# SCH_Schematic-PCB-Design-FC-TD2_2026-04-.net
KiCad netlist of a schematic drawn in EasyEDA
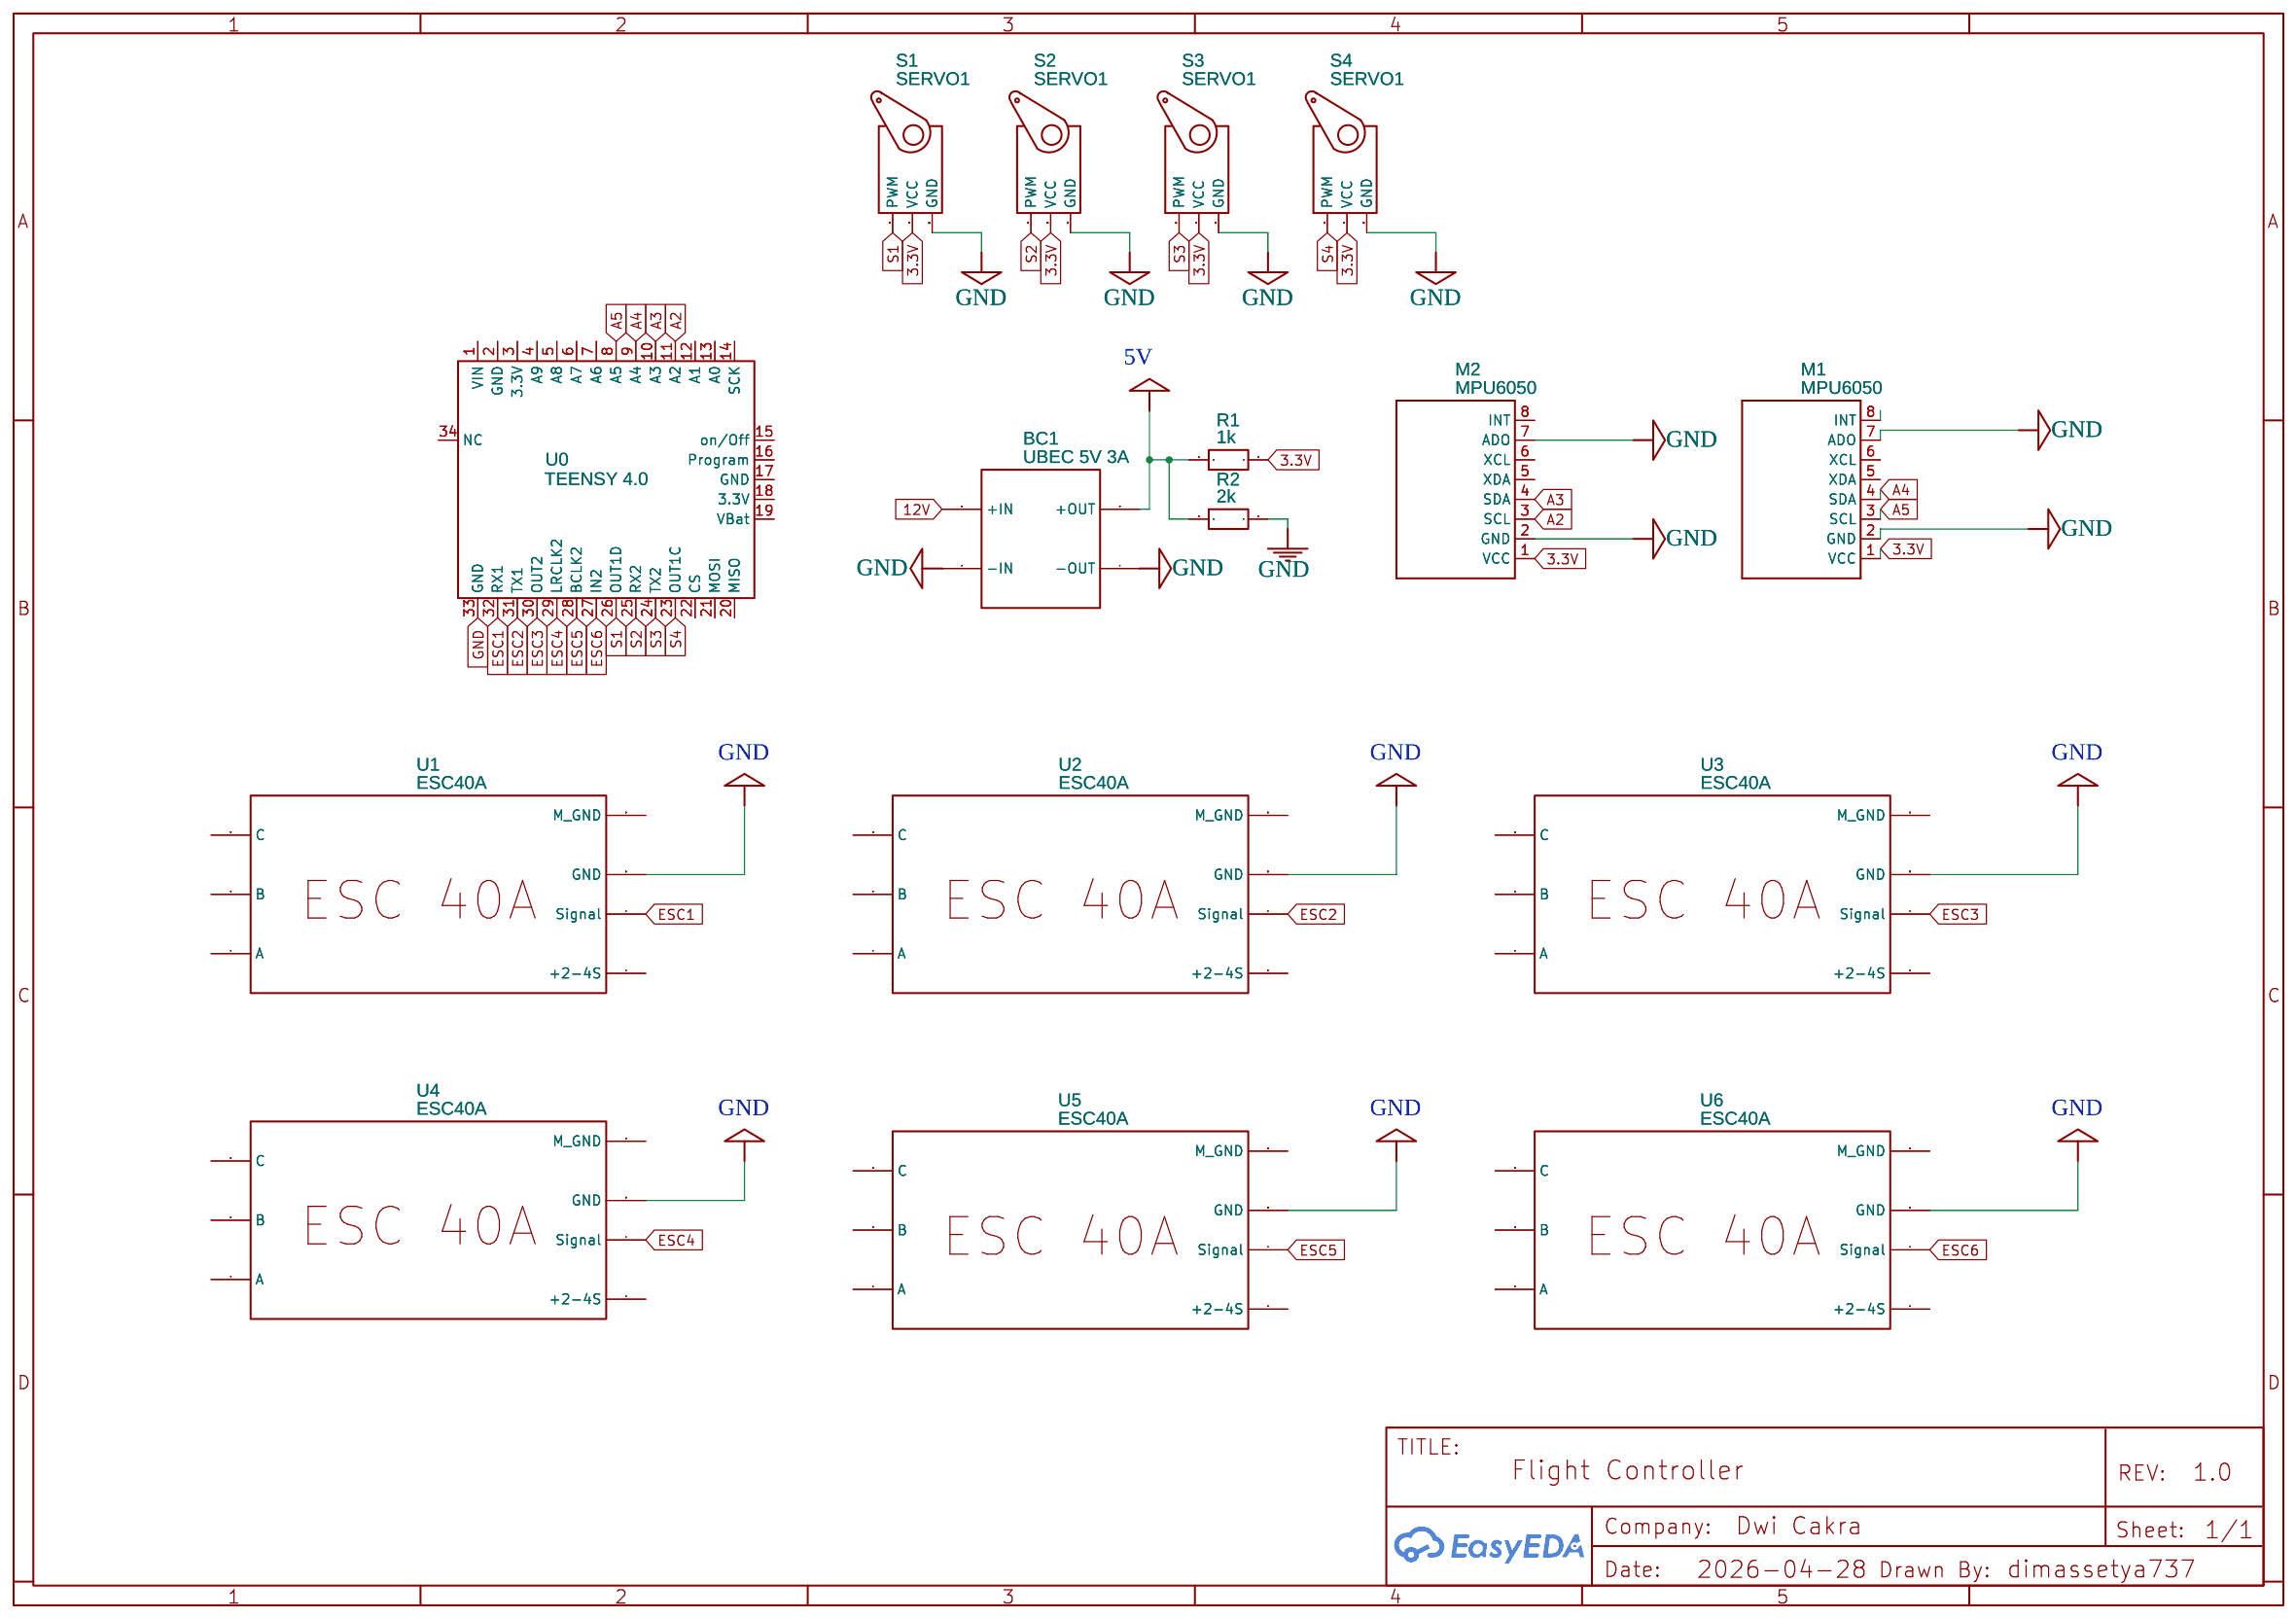
[diagram p0: schematic sheet]

(export (version "E")
  (design (tool "Eeschema 10.0.6"))
  (components
    (comp (ref "BC1") (value "UBEC 5V 3A") (libsource (lib "") (part "UBEC 5V 3A")))
    (comp (ref "M1") (value "MPU6050") (libsource (lib "") (part "MPU6050")))
    (comp (ref "M2") (value "MPU6050") (libsource (lib "") (part "MPU6050")))
    (comp (ref "R1")
      (value "1k")
      (fields (field (name "Manufacturer Part") "贴片电阻ChipResistors"))
      (libsource (lib "") (part "贴片电阻CHIPRESISTORS"))
    )
    (comp (ref "R2")
      (value "2k")
      (fields (field (name "Manufacturer Part") "贴片电阻ChipResistors"))
      (libsource (lib "") (part "贴片电阻CHIPRESISTORS"))
    )
    (comp (ref "S1") (value "SERVO1") (libsource (lib "") (part "SERVO MG90S")))
    (comp (ref "S2") (value "SERVO1") (libsource (lib "") (part "SERVO MG90S")))
    (comp (ref "S3") (value "SERVO1") (libsource (lib "") (part "SERVO MG90S")))
    (comp (ref "S4") (value "SERVO1") (libsource (lib "") (part "SERVO MG90S")))
    (comp (ref "U0")
      (value "TEENSY 4.0")
      (fields (field (name "Manufacturer Part") "Teensy 4.0"))
      (libsource (lib "") (part "TEENSY 4.0"))
    )
    (comp (ref "U1") (value "ESC40A") (libsource (lib "") (part "ESC40A_1")))
    (comp (ref "U2") (value "ESC40A") (libsource (lib "") (part "ESC40A_1")))
    (comp (ref "U3") (value "ESC40A") (libsource (lib "") (part "ESC40A_1")))
    (comp (ref "U4") (value "ESC40A") (libsource (lib "") (part "ESC40A_1")))
    (comp (ref "U5") (value "ESC40A") (libsource (lib "") (part "ESC40A")))
    (comp (ref "U6") (value "ESC40A") (libsource (lib "") (part "ESC40A")))
  )
  (nets
    (net (code "1") (name "3.3V") (class "Default")
      (node (ref "M1") (pin "1") (pinfunction "VCC_1") (pintype "bidirectional"))
      (node (ref "M2") (pin "1") (pinfunction "VCC_1") (pintype "bidirectional"))
      (node (ref "R1") (pin "2") (pinfunction "2_2") (pintype "unspecified"))
      (node (ref "S1") (pin "VCC") (pinfunction "VCC_VCC") (pintype "unspecified"))
      (node (ref "S2") (pin "VCC") (pinfunction "VCC_VCC") (pintype "unspecified"))
      (node (ref "S3") (pin "VCC") (pinfunction "VCC_VCC") (pintype "unspecified"))
      (node (ref "S4") (pin "VCC") (pinfunction "VCC_VCC") (pintype "unspecified"))
    )
    (net (code "2") (name "5V") (class "Default")
      (node (ref "BC1") (pin "3") (pinfunction "+OUT_3") (pintype "unspecified"))
      (node (ref "R1") (pin "1") (pinfunction "1_1") (pintype "unspecified"))
      (node (ref "R2") (pin "1") (pinfunction "1_1") (pintype "unspecified"))
    )
    (net (code "3") (name "12V") (class "Default")
      (node (ref "BC1") (pin "2") (pinfunction "+IN_2") (pintype "unspecified"))
    )
    (net (code "4") (name "A2") (class "Default")
      (node (ref "M2") (pin "3") (pinfunction "SCL_3") (pintype "bidirectional"))
      (node (ref "U0") (pin "11") (pinfunction "A2_11") (pintype "unspecified"))
    )
    (net (code "5") (name "A3") (class "Default")
      (node (ref "M2") (pin "4") (pinfunction "SDA_4") (pintype "bidirectional"))
      (node (ref "U0") (pin "10") (pinfunction "A3_10") (pintype "unspecified"))
    )
    (net (code "6") (name "A4") (class "Default")
      (node (ref "M1") (pin "4") (pinfunction "SDA_4") (pintype "bidirectional"))
      (node (ref "U0") (pin "9") (pinfunction "A4_9") (pintype "unspecified"))
    )
    (net (code "7") (name "A5") (class "Default")
      (node (ref "M1") (pin "3") (pinfunction "SCL_3") (pintype "bidirectional"))
      (node (ref "U0") (pin "8") (pinfunction "A5_8") (pintype "unspecified"))
    )
    (net (code "8") (name "ESC1") (class "Default")
      (node (ref "U0") (pin "32") (pinfunction "RX1_32") (pintype "unspecified"))
      (node (ref "U1") (pin "7") (pinfunction "Signal_7") (pintype "unspecified"))
    )
    (net (code "9") (name "ESC2") (class "Default")
      (node (ref "U0") (pin "31") (pinfunction "TX1_31") (pintype "unspecified"))
      (node (ref "U2") (pin "7") (pinfunction "Signal_7") (pintype "unspecified"))
    )
    (net (code "10") (name "ESC3") (class "Default")
      (node (ref "U0") (pin "30") (pinfunction "OUT2_30") (pintype "unspecified"))
      (node (ref "U3") (pin "7") (pinfunction "Signal_7") (pintype "unspecified"))
    )
    (net (code "11") (name "ESC4") (class "Default")
      (node (ref "U0") (pin "29") (pinfunction "LRCLK2_29") (pintype "unspecified"))
      (node (ref "U4") (pin "7") (pinfunction "Signal_7") (pintype "unspecified"))
    )
    (net (code "12") (name "ESC5") (class "Default")
      (node (ref "U0") (pin "28") (pinfunction "BCLK2_28") (pintype "unspecified"))
      (node (ref "U5") (pin "7") (pinfunction "Signal_7") (pintype "unspecified"))
    )
    (net (code "13") (name "ESC6") (class "Default")
      (node (ref "U0") (pin "27") (pinfunction "IN2_27") (pintype "unspecified"))
      (node (ref "U6") (pin "7") (pinfunction "Signal_7") (pintype "unspecified"))
    )
    (net (code "14") (name "GND") (class "Default")
      (node (ref "BC1") (pin "1") (pinfunction "-IN_1") (pintype "unspecified"))
      (node (ref "BC1") (pin "4") (pinfunction "-OUT_4") (pintype "unspecified"))
      (node (ref "M1") (pin "2") (pinfunction "GND_2") (pintype "bidirectional"))
      (node (ref "M1") (pin "7") (pinfunction "ADO_7") (pintype "bidirectional"))
      (node (ref "M2") (pin "2") (pinfunction "GND_2") (pintype "bidirectional"))
      (node (ref "M2") (pin "7") (pinfunction "ADO_7") (pintype "bidirectional"))
      (node (ref "R2") (pin "2") (pinfunction "2_2") (pintype "unspecified"))
      (node (ref "S1") (pin "GND") (pinfunction "GND_GND") (pintype "unspecified"))
      (node (ref "S2") (pin "GND") (pinfunction "GND_GND") (pintype "unspecified"))
      (node (ref "S3") (pin "GND") (pinfunction "GND_GND") (pintype "unspecified"))
      (node (ref "S4") (pin "GND") (pinfunction "GND_GND") (pintype "unspecified"))
      (node (ref "U0") (pin "33") (pinfunction "GND_33") (pintype "unspecified"))
      (node (ref "U1") (pin "6") (pinfunction "GND_6") (pintype "unspecified"))
      (node (ref "U2") (pin "6") (pinfunction "GND_6") (pintype "unspecified"))
      (node (ref "U3") (pin "6") (pinfunction "GND_6") (pintype "unspecified"))
      (node (ref "U4") (pin "6") (pinfunction "GND_6") (pintype "unspecified"))
      (node (ref "U5") (pin "6") (pinfunction "GND_6") (pintype "unspecified"))
      (node (ref "U6") (pin "6") (pinfunction "GND_6") (pintype "unspecified"))
    )
    (net (code "15") (name "S1") (class "Default")
      (node (ref "S1") (pin "PWM") (pinfunction "PWM_PWM") (pintype "unspecified"))
      (node (ref "U0") (pin "26") (pinfunction "OUT1D_26") (pintype "unspecified"))
    )
    (net (code "16") (name "S2") (class "Default")
      (node (ref "S2") (pin "PWM") (pinfunction "PWM_PWM") (pintype "unspecified"))
      (node (ref "U0") (pin "25") (pinfunction "RX2_25") (pintype "unspecified"))
    )
    (net (code "17") (name "S3") (class "Default")
      (node (ref "S3") (pin "PWM") (pinfunction "PWM_PWM") (pintype "unspecified"))
      (node (ref "U0") (pin "24") (pinfunction "TX2_24") (pintype "unspecified"))
    )
    (net (code "18") (name "S4") (class "Default")
      (node (ref "S4") (pin "PWM") (pinfunction "PWM_PWM") (pintype "unspecified"))
      (node (ref "U0") (pin "23") (pinfunction "OUT1C_23") (pintype "unspecified"))
    )
    (net (code "19") (name "unconnected-(M1-INT-Pad8)") (class "Default")
      (node (ref "M1") (pin "8") (pinfunction "INT_8") (pintype "bidirectional"))
    )
    (net (code "20") (name "unconnected-(M1-XCL-Pad6)") (class "Default")
      (node (ref "M1") (pin "6") (pinfunction "XCL_6") (pintype "bidirectional"))
    )
    (net (code "21") (name "unconnected-(M1-XDA-Pad5)") (class "Default")
      (node (ref "M1") (pin "5") (pinfunction "XDA_5") (pintype "bidirectional"))
    )
    (net (code "22") (name "unconnected-(M2-INT-Pad8)") (class "Default")
      (node (ref "M2") (pin "8") (pinfunction "INT_8") (pintype "bidirectional"))
    )
    (net (code "23") (name "unconnected-(M2-XCL-Pad6)") (class "Default")
      (node (ref "M2") (pin "6") (pinfunction "XCL_6") (pintype "bidirectional"))
    )
    (net (code "24") (name "unconnected-(M2-XDA-Pad5)") (class "Default")
      (node (ref "M2") (pin "5") (pinfunction "XDA_5") (pintype "bidirectional"))
    )
    (net (code "25") (name "unconnected-(U0-3.3V-Pad3)") (class "Default")
      (node (ref "U0") (pin "3") (pinfunction "3.3V_3") (pintype "unspecified"))
    )
    (net (code "26") (name "unconnected-(U0-3.3V-Pad18)") (class "Default")
      (node (ref "U0") (pin "18") (pinfunction "3.3V_18") (pintype "unspecified"))
    )
    (net (code "27") (name "unconnected-(U0-A0-Pad13)") (class "Default")
      (node (ref "U0") (pin "13") (pinfunction "A0_13") (pintype "unspecified"))
    )
    (net (code "28") (name "unconnected-(U0-A1-Pad12)") (class "Default")
      (node (ref "U0") (pin "12") (pinfunction "A1_12") (pintype "unspecified"))
    )
    (net (code "29") (name "unconnected-(U0-A6-Pad7)") (class "Default")
      (node (ref "U0") (pin "7") (pinfunction "A6_7") (pintype "unspecified"))
    )
    (net (code "30") (name "unconnected-(U0-A7-Pad6)") (class "Default")
      (node (ref "U0") (pin "6") (pinfunction "A7_6") (pintype "unspecified"))
    )
    (net (code "31") (name "unconnected-(U0-A8-Pad5)") (class "Default")
      (node (ref "U0") (pin "5") (pinfunction "A8_5") (pintype "unspecified"))
    )
    (net (code "32") (name "unconnected-(U0-A9-Pad4)") (class "Default")
      (node (ref "U0") (pin "4") (pinfunction "A9_4") (pintype "unspecified"))
    )
    (net (code "33") (name "unconnected-(U0-CS-Pad22)") (class "Default")
      (node (ref "U0") (pin "22") (pinfunction "CS_22") (pintype "unspecified"))
    )
    (net (code "34") (name "unconnected-(U0-GND-Pad2)") (class "Default")
      (node (ref "U0") (pin "2") (pinfunction "GND_2") (pintype "unspecified"))
    )
    (net (code "35") (name "unconnected-(U0-GND-Pad17)") (class "Default")
      (node (ref "U0") (pin "17") (pinfunction "GND_17") (pintype "unspecified"))
    )
    (net (code "36") (name "unconnected-(U0-MISO-Pad20)") (class "Default")
      (node (ref "U0") (pin "20") (pinfunction "MISO_20") (pintype "unspecified"))
    )
    (net (code "37") (name "unconnected-(U0-MOSI-Pad21)") (class "Default")
      (node (ref "U0") (pin "21") (pinfunction "MOSI_21") (pintype "unspecified"))
    )
    (net (code "38") (name "unconnected-(U0-NC-Pad34)") (class "Default")
      (node (ref "U0") (pin "34") (pinfunction "NC_34") (pintype "unspecified"))
    )
    (net (code "39") (name "unconnected-(U0-Program-Pad16)") (class "Default")
      (node (ref "U0") (pin "16") (pinfunction "Program_16") (pintype "unspecified"))
    )
    (net (code "40") (name "unconnected-(U0-SCK-Pad14)") (class "Default")
      (node (ref "U0") (pin "14") (pinfunction "SCK_14") (pintype "unspecified"))
    )
    (net (code "41") (name "unconnected-(U0-VBat-Pad19)") (class "Default")
      (node (ref "U0") (pin "19") (pinfunction "VBat_19") (pintype "unspecified"))
    )
    (net (code "42") (name "unconnected-(U0-VIN-Pad1)") (class "Default")
      (node (ref "U0") (pin "1") (pinfunction "VIN_1") (pintype "unspecified"))
    )
    (net (code "43") (name "unconnected-(U0-on{slash}Off-Pad15)") (class "Default")
      (node (ref "U0") (pin "15") (pinfunction "on/Off_15") (pintype "unspecified"))
    )
    (net (code "44") (name "unconnected-(U1-+2-4S-Pad4)") (class "Default")
      (node (ref "U1") (pin "4") (pinfunction "+2-4S_4") (pintype "unspecified"))
    )
    (net (code "45") (name "unconnected-(U1-A-Pad1)") (class "Default")
      (node (ref "U1") (pin "1") (pinfunction "A_1") (pintype "unspecified"))
    )
    (net (code "46") (name "unconnected-(U1-B-Pad2)") (class "Default")
      (node (ref "U1") (pin "2") (pinfunction "B_2") (pintype "unspecified"))
    )
    (net (code "47") (name "unconnected-(U1-C-Pad3)") (class "Default")
      (node (ref "U1") (pin "3") (pinfunction "C_3") (pintype "unspecified"))
    )
    (net (code "48") (name "unconnected-(U1-M_GND-Pad5)") (class "Default")
      (node (ref "U1") (pin "5") (pinfunction "M_GND_5") (pintype "unspecified"))
    )
    (net (code "49") (name "unconnected-(U2-+2-4S-Pad4)") (class "Default")
      (node (ref "U2") (pin "4") (pinfunction "+2-4S_4") (pintype "unspecified"))
    )
    (net (code "50") (name "unconnected-(U2-A-Pad1)") (class "Default")
      (node (ref "U2") (pin "1") (pinfunction "A_1") (pintype "unspecified"))
    )
    (net (code "51") (name "unconnected-(U2-B-Pad2)") (class "Default")
      (node (ref "U2") (pin "2") (pinfunction "B_2") (pintype "unspecified"))
    )
    (net (code "52") (name "unconnected-(U2-C-Pad3)") (class "Default")
      (node (ref "U2") (pin "3") (pinfunction "C_3") (pintype "unspecified"))
    )
    (net (code "53") (name "unconnected-(U2-M_GND-Pad5)") (class "Default")
      (node (ref "U2") (pin "5") (pinfunction "M_GND_5") (pintype "unspecified"))
    )
    (net (code "54") (name "unconnected-(U3-+2-4S-Pad4)") (class "Default")
      (node (ref "U3") (pin "4") (pinfunction "+2-4S_4") (pintype "unspecified"))
    )
    (net (code "55") (name "unconnected-(U3-A-Pad1)") (class "Default")
      (node (ref "U3") (pin "1") (pinfunction "A_1") (pintype "unspecified"))
    )
    (net (code "56") (name "unconnected-(U3-B-Pad2)") (class "Default")
      (node (ref "U3") (pin "2") (pinfunction "B_2") (pintype "unspecified"))
    )
    (net (code "57") (name "unconnected-(U3-C-Pad3)") (class "Default")
      (node (ref "U3") (pin "3") (pinfunction "C_3") (pintype "unspecified"))
    )
    (net (code "58") (name "unconnected-(U3-M_GND-Pad5)") (class "Default")
      (node (ref "U3") (pin "5") (pinfunction "M_GND_5") (pintype "unspecified"))
    )
    (net (code "59") (name "unconnected-(U4-+2-4S-Pad4)") (class "Default")
      (node (ref "U4") (pin "4") (pinfunction "+2-4S_4") (pintype "unspecified"))
    )
    (net (code "60") (name "unconnected-(U4-A-Pad1)") (class "Default")
      (node (ref "U4") (pin "1") (pinfunction "A_1") (pintype "unspecified"))
    )
    (net (code "61") (name "unconnected-(U4-B-Pad2)") (class "Default")
      (node (ref "U4") (pin "2") (pinfunction "B_2") (pintype "unspecified"))
    )
    (net (code "62") (name "unconnected-(U4-C-Pad3)") (class "Default")
      (node (ref "U4") (pin "3") (pinfunction "C_3") (pintype "unspecified"))
    )
    (net (code "63") (name "unconnected-(U4-M_GND-Pad5)") (class "Default")
      (node (ref "U4") (pin "5") (pinfunction "M_GND_5") (pintype "unspecified"))
    )
    (net (code "64") (name "unconnected-(U5-+2-4S-Pad4)") (class "Default")
      (node (ref "U5") (pin "4") (pinfunction "+2-4S_4") (pintype "unspecified"))
    )
    (net (code "65") (name "unconnected-(U5-A-Pad1)") (class "Default")
      (node (ref "U5") (pin "1") (pinfunction "A_1") (pintype "unspecified"))
    )
    (net (code "66") (name "unconnected-(U5-B-Pad2)") (class "Default")
      (node (ref "U5") (pin "2") (pinfunction "B_2") (pintype "unspecified"))
    )
    (net (code "67") (name "unconnected-(U5-C-Pad3)") (class "Default")
      (node (ref "U5") (pin "3") (pinfunction "C_3") (pintype "unspecified"))
    )
    (net (code "68") (name "unconnected-(U5-M_GND-Pad5)") (class "Default")
      (node (ref "U5") (pin "5") (pinfunction "M_GND_5") (pintype "unspecified"))
    )
    (net (code "69") (name "unconnected-(U6-+2-4S-Pad4)") (class "Default")
      (node (ref "U6") (pin "4") (pinfunction "+2-4S_4") (pintype "unspecified"))
    )
    (net (code "70") (name "unconnected-(U6-A-Pad1)") (class "Default")
      (node (ref "U6") (pin "1") (pinfunction "A_1") (pintype "unspecified"))
    )
    (net (code "71") (name "unconnected-(U6-B-Pad2)") (class "Default")
      (node (ref "U6") (pin "2") (pinfunction "B_2") (pintype "unspecified"))
    )
    (net (code "72") (name "unconnected-(U6-C-Pad3)") (class "Default")
      (node (ref "U6") (pin "3") (pinfunction "C_3") (pintype "unspecified"))
    )
    (net (code "73") (name "unconnected-(U6-M_GND-Pad5)") (class "Default")
      (node (ref "U6") (pin "5") (pinfunction "M_GND_5") (pintype "unspecified"))
    )
  )
)
